# Bias_Lighting_Controller_Schematic.net
KiCad netlist of a schematic drawn in EAGLE
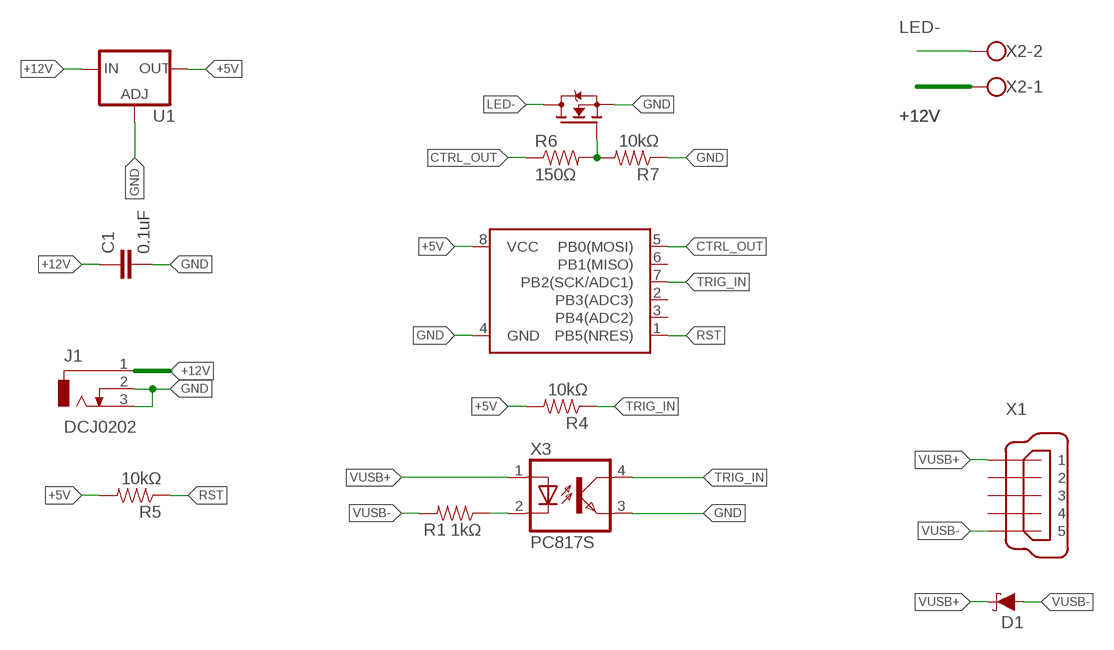
[diagram p0: schematic, sheet 1]

(export (version "E")
  (design (tool "Eeschema 10.0.6"))
  (components
    (comp (ref "ATTINY85")
      (value "ATTINY45")
      (footprint "eagle-import:SO08-EIAJ")
      (libsource (lib "eagle-import") (part "ATTINY45"))
    )
    (comp (ref "C1")
      (value "0.1uF")
      (footprint "eagle-import:C1206K")
      (libsource (lib "eagle-import") (part "C-EUC1206K"))
    )
    (comp (ref "D1")
      (value "DIODE-SCHOTTKY-SS14")
      (footprint "eagle-import:SMA-DIODE")
      (libsource (lib "eagle-import") (part "DIODE-SCHOTTKY-SS14"))
    )
    (comp (ref "IRF740_MOSFET1")
      (value "MOSFET-N-SOT23")
      (footprint "eagle-import:SOT23")
      (libsource (lib "eagle-import") (part "MOSFET-N-SOT23"))
    )
    (comp (ref "J1")
      (value "DCJ0202")
      (footprint "eagle-import:DCJ0202")
      (libsource (lib "eagle-import") (part "DCJ0202"))
    )
    (comp (ref "R1")
      (value "1kΩ")
      (footprint "eagle-import:1206")
      (libsource (lib "eagle-import") (part "RESISTOR1206"))
    )
    (comp (ref "R4")
      (value "10kΩ")
      (footprint "eagle-import:1206")
      (libsource (lib "eagle-import") (part "RESISTOR1206"))
    )
    (comp (ref "R5")
      (value "10kΩ")
      (footprint "eagle-import:1206")
      (libsource (lib "eagle-import") (part "RESISTOR1206"))
    )
    (comp (ref "R6")
      (value "150Ω")
      (footprint "eagle-import:1206")
      (libsource (lib "eagle-import") (part "RESISTOR1206"))
    )
    (comp (ref "R7")
      (value "10kΩ")
      (footprint "eagle-import:1206")
      (libsource (lib "eagle-import") (part "RESISTOR1206"))
    )
    (comp (ref "U1")
      (value "V_REG_317SMD")
      (footprint "eagle-import:SOT223")
      (libsource (lib "eagle-import") (part "V_REG_317SMD"))
    )
    (comp (ref "X1")
      (value "MINI-USB-UX60-MB-5ST")
      (footprint "eagle-import:UX60-MB-5ST")
      (libsource (lib "eagle-import") (part "MINI-USB-UX60-MB-5ST"))
    )
    (comp (ref "X2")
      (value "W237-102")
      (footprint "eagle-import:W237-102")
      (fields (field (name "MPN") "237-102"))
      (libsource (lib "eagle-import") (part "W237-102"))
    )
    (comp (ref "X3")
      (value "PC817S")
      (footprint "eagle-import:PC817SMT")
      (libsource (lib "eagle-import") (part "PC817S"))
    )
  )
  (nets
    (net (code "1") (name "+5V") (class "Default")
      (node (ref "ATTINY85") (pin "8") (pinfunction "VCC_8") (pintype "bidirectional"))
      (node (ref "R4") (pin "2") (pinfunction "2_2") (pintype "passive"))
      (node (ref "R5") (pin "2") (pinfunction "2_2") (pintype "passive"))
      (node (ref "U1") (pin "2") (pinfunction "OUT_2") (pintype "output"))
    )
    (net (code "2") (name "+12V") (class "Default")
      (node (ref "C1") (pin "1") (pinfunction "1_1") (pintype "passive"))
      (node (ref "J1") (pin "1") (pinfunction "1_1") (pintype "passive"))
      (node (ref "U1") (pin "3") (pinfunction "IN_3") (pintype "input"))
      (node (ref "X2") (pin "1") (pinfunction "KL_1") (pintype "passive"))
    )
    (net (code "3") (name "CTRL_OUT") (class "Default")
      (node (ref "ATTINY85") (pin "5") (pinfunction "PB0(MOSI)_5") (pintype "bidirectional"))
      (node (ref "R6") (pin "1") (pinfunction "1_1") (pintype "passive"))
    )
    (net (code "4") (name "GND") (class "Default")
      (node (ref "ATTINY85") (pin "4") (pinfunction "GND_4") (pintype "bidirectional"))
      (node (ref "C1") (pin "2") (pinfunction "2_2") (pintype "passive"))
      (node (ref "IRF740_MOSFET1") (pin "2") (pinfunction "S_2") (pintype "passive"))
      (node (ref "J1") (pin "2") (pinfunction "2_2") (pintype "passive"))
      (node (ref "J1") (pin "3") (pinfunction "3_3") (pintype "passive"))
      (node (ref "R7") (pin "1") (pinfunction "1_1") (pintype "passive"))
      (node (ref "U1") (pin "1") (pinfunction "ADJ_1") (pintype "input"))
      (node (ref "X3") (pin "3") (pinfunction "EMIT_3") (pintype "passive"))
    )
    (net (code "5") (name "LED-") (class "Default")
      (node (ref "IRF740_MOSFET1") (pin "3") (pinfunction "D_3") (pintype "passive"))
      (node (ref "X2") (pin "2") (pinfunction "KL_2") (pintype "passive"))
    )
    (net (code "6") (name "Net-(IRF740_MOSFET1-G)") (class "Default")
      (node (ref "IRF740_MOSFET1") (pin "1") (pinfunction "G_1") (pintype "passive"))
      (node (ref "R6") (pin "2") (pinfunction "2_2") (pintype "passive"))
      (node (ref "R7") (pin "2") (pinfunction "2_2") (pintype "passive"))
    )
    (net (code "7") (name "Net-(X3-C)") (class "Default")
      (node (ref "R1") (pin "1") (pinfunction "1_1") (pintype "passive"))
      (node (ref "X3") (pin "2") (pinfunction "C_2") (pintype "passive"))
    )
    (net (code "8") (name "RST") (class "Default")
      (node (ref "ATTINY85") (pin "1") (pinfunction "PB5(NRES)_1") (pintype "bidirectional"))
      (node (ref "R5") (pin "1") (pinfunction "1_1") (pintype "passive"))
    )
    (net (code "9") (name "TRIG_IN") (class "Default")
      (node (ref "ATTINY85") (pin "7") (pinfunction "PB2(SCK/ADC1)_7") (pintype "bidirectional"))
      (node (ref "R4") (pin "1") (pinfunction "1_1") (pintype "passive"))
      (node (ref "X3") (pin "4") (pinfunction "COL_4") (pintype "passive"))
    )
    (net (code "10") (name "VUSB+") (class "Default")
      (node (ref "D1") (pin "C") (pinfunction "C_C") (pintype "passive"))
      (node (ref "X1") (pin "1") (pinfunction "1_1") (pintype "input"))
      (node (ref "X3") (pin "1") (pinfunction "A_1") (pintype "passive"))
    )
    (net (code "11") (name "VUSB-") (class "Default")
      (node (ref "D1") (pin "A") (pinfunction "A_A") (pintype "passive"))
      (node (ref "R1") (pin "2") (pinfunction "2_2") (pintype "passive"))
      (node (ref "X1") (pin "5") (pinfunction "5_5") (pintype "input"))
    )
    (net (code "12") (name "unconnected-(ATTINY85-PB1(MISO)-Pad6)") (class "Default")
      (node (ref "ATTINY85") (pin "6") (pinfunction "PB1(MISO)_6") (pintype "bidirectional"))
    )
    (net (code "13") (name "unconnected-(ATTINY85-PB3(ADC3)-Pad2)") (class "Default")
      (node (ref "ATTINY85") (pin "2") (pinfunction "PB3(ADC3)_2") (pintype "bidirectional"))
    )
    (net (code "14") (name "unconnected-(ATTINY85-PB4(ADC2)-Pad3)") (class "Default")
      (node (ref "ATTINY85") (pin "3") (pinfunction "PB4(ADC2)_3") (pintype "bidirectional"))
    )
    (net (code "15") (name "unconnected-(X1-Pad2)") (class "Default")
      (node (ref "X1") (pin "2") (pinfunction "2_2") (pintype "input"))
    )
    (net (code "16") (name "unconnected-(X1-Pad3)") (class "Default")
      (node (ref "X1") (pin "3") (pinfunction "3_3") (pintype "input"))
    )
    (net (code "17") (name "unconnected-(X1-Pad4)") (class "Default")
      (node (ref "X1") (pin "4") (pinfunction "4_4") (pintype "input"))
    )
  )
)
